# Power.net
KiCad netlist of a schematic drawn in Altium Designer
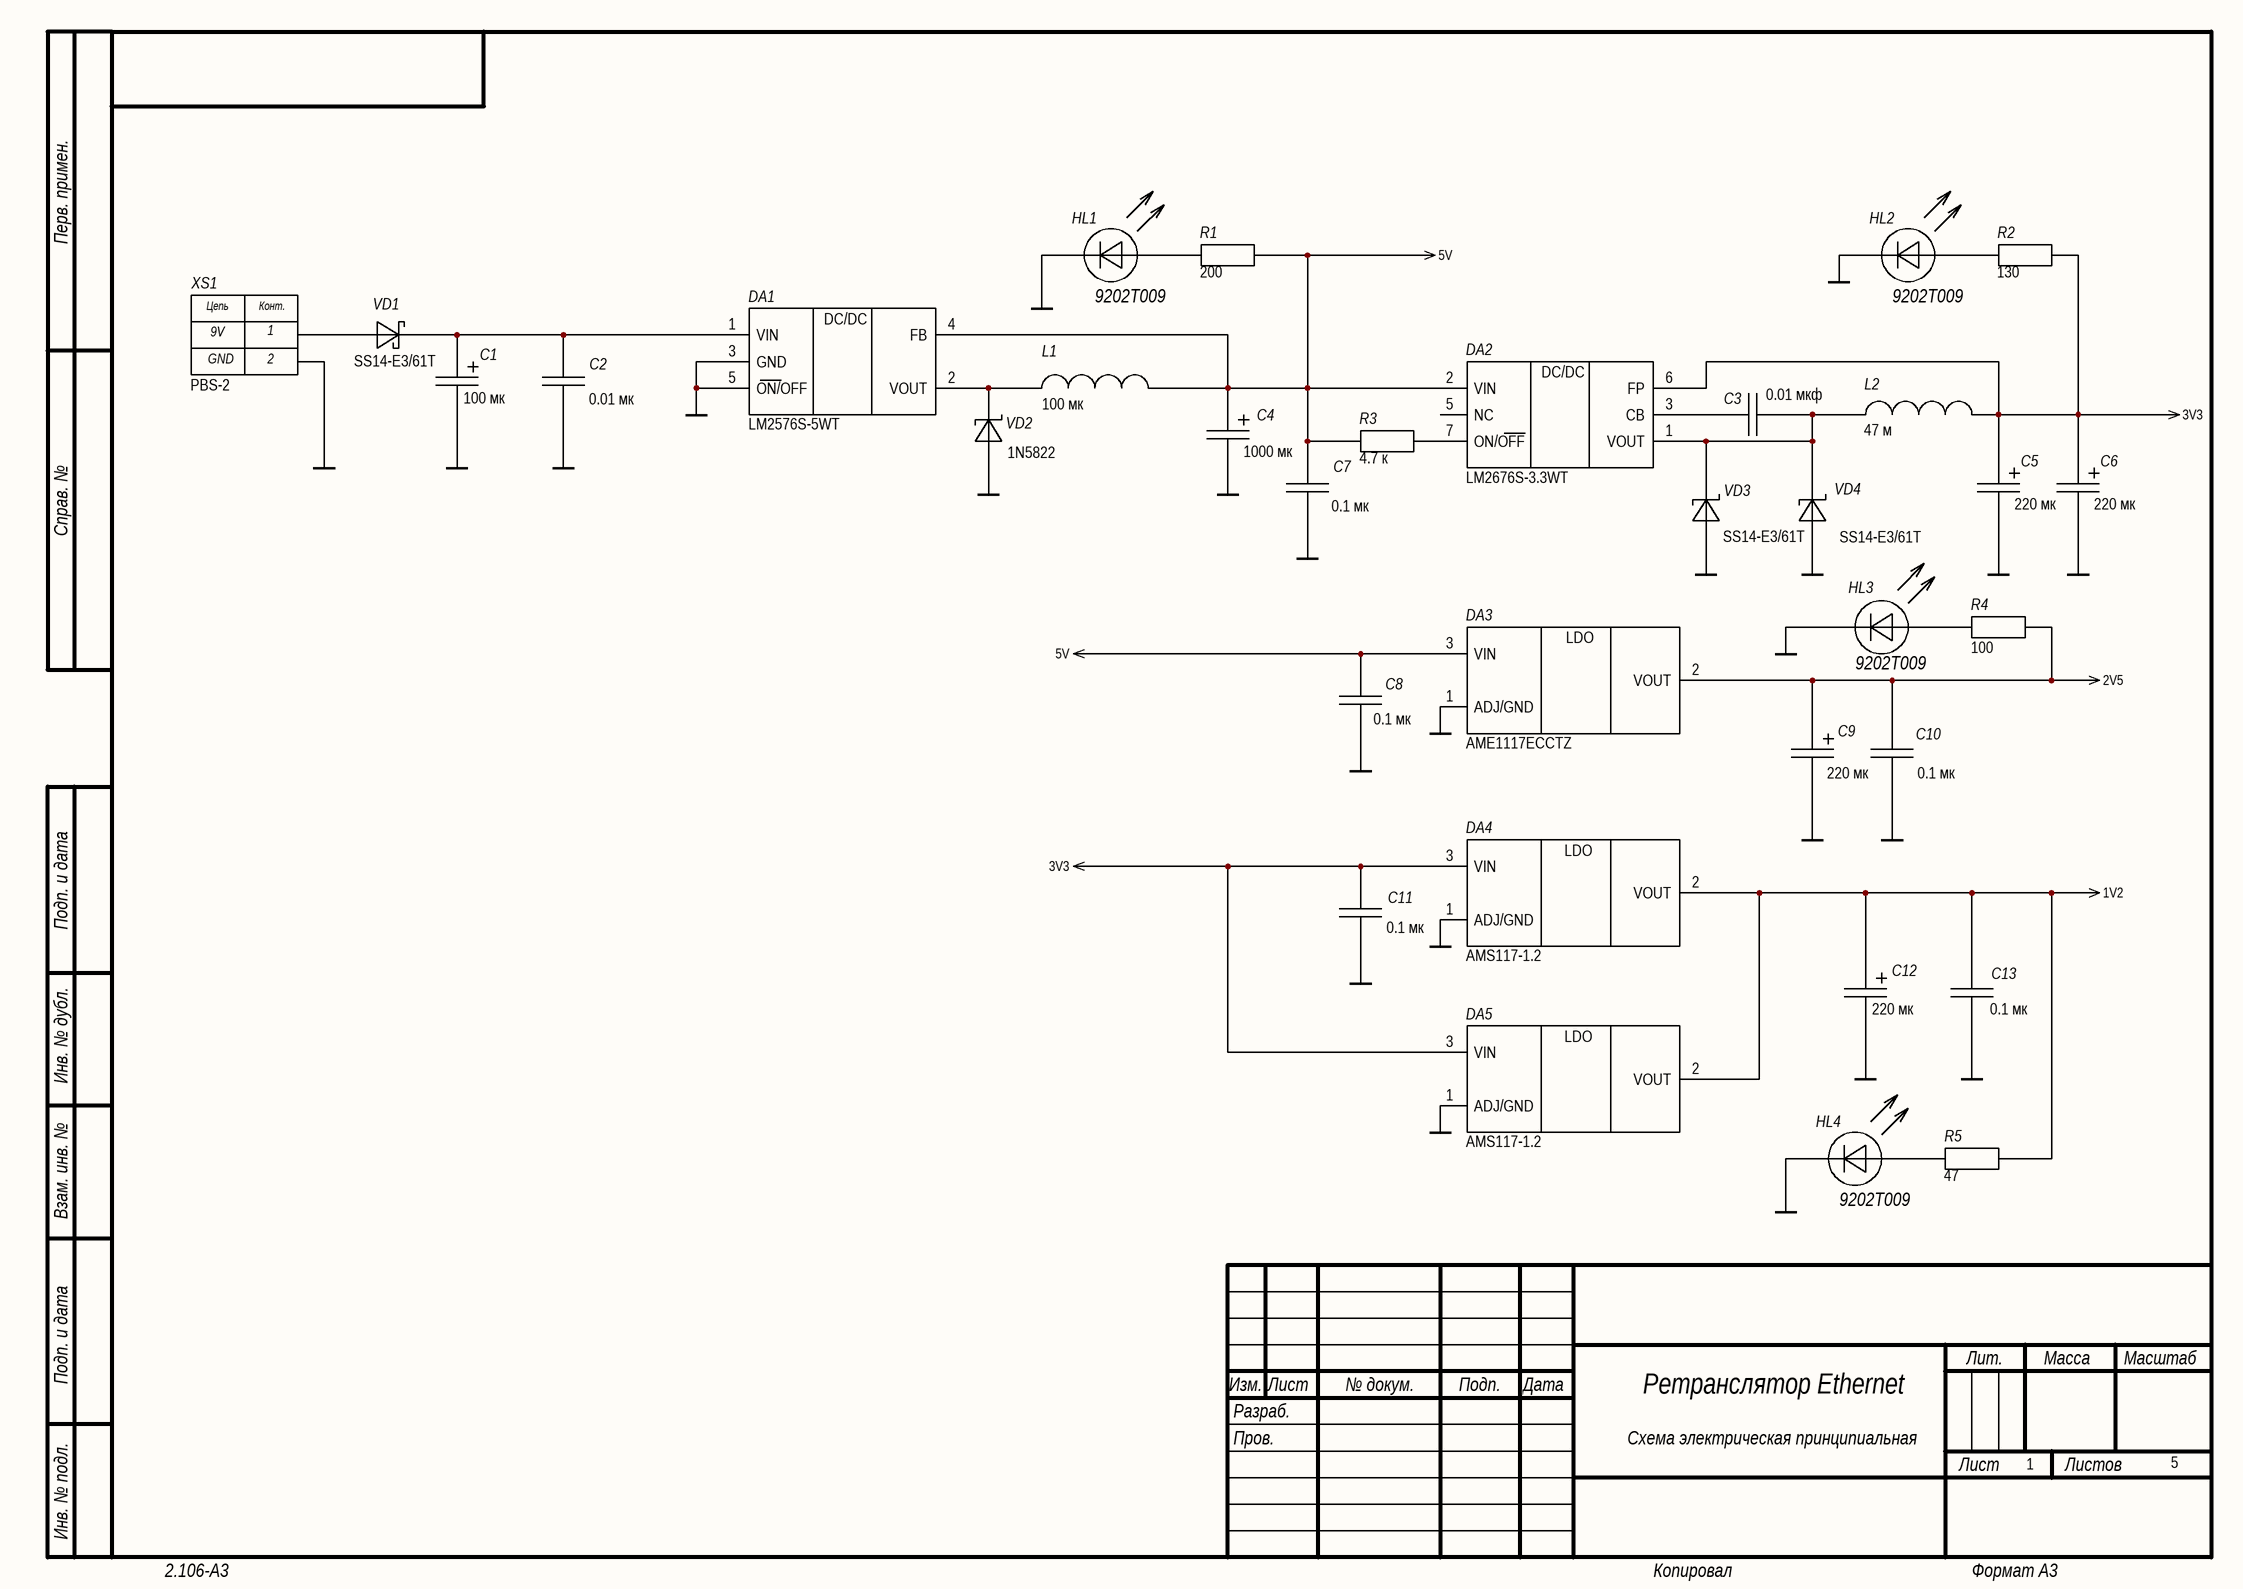
[diagram p0: Power.SchDoc]

(export (version "E")
  (design (tool "Eeschema 10.0.6"))
  (components
    (comp (ref "C1") (value "~") (libsource (lib "Schlib1") (part "C_POL")))
    (comp (ref "C2") (value "~") (libsource (lib "Schlib1") (part "C")))
    (comp (ref "C3") (value "~") (libsource (lib "Schlib1") (part "C")))
    (comp (ref "C4") (value "~") (libsource (lib "Schlib1") (part "C_POL")))
    (comp (ref "C5") (value "~") (libsource (lib "Schlib1") (part "C_POL")))
    (comp (ref "C6") (value "~") (libsource (lib "Schlib1") (part "C_POL")))
    (comp (ref "C7") (value "~") (libsource (lib "Schlib1") (part "C")))
    (comp (ref "C8") (value "~") (libsource (lib "Schlib1") (part "C")))
    (comp (ref "C9") (value "~") (libsource (lib "Schlib1") (part "C_POL")))
    (comp (ref "C10") (value "~") (libsource (lib "Schlib1") (part "C")))
    (comp (ref "C11") (value "~") (libsource (lib "Schlib1") (part "C")))
    (comp (ref "C12") (value "~") (libsource (lib "Schlib1") (part "C_POL")))
    (comp (ref "C13") (value "~") (libsource (lib "Schlib1") (part "C")))
    (comp (ref "DA1") (value "LM2576S-5WT") (libsource (lib "Schlib1") (part "LM2576_DCDC")))
    (comp (ref "DA2") (value "LM2676S-3.3WT") (libsource (lib "Schlib1") (part "LM2676_LDO_3v3")))
    (comp (ref "DA3") (value "AME1117ECCTZ") (libsource (lib "Schlib1") (part "AME1117ECCTZ_LDO_1.8v")))
    (comp (ref "DA4") (value "AMS117-1.2") (libsource (lib "Schlib1") (part "AME1117ACCTZ_LDO_1.2v")))
    (comp (ref "DA5") (value "AMS117-1.2") (libsource (lib "Schlib1") (part "AME1117ACCTZ_LDO_1.2v")))
    (comp (ref "HL1")
      (value "9202T009")
      (fields (field (name "VALUEMANUFACTURERPARTNUMBER") "fyls-0603urc"))
      (libsource (lib "Schlib1") (part "Led_blue"))
    )
    (comp (ref "HL2")
      (value "9202T009")
      (fields (field (name "VALUEMANUFACTURERPARTNUMBER") "fyls-0603urc"))
      (libsource (lib "Schlib1") (part "Led_blue"))
    )
    (comp (ref "HL3")
      (value "9202T009")
      (fields (field (name "VALUEMANUFACTURERPARTNUMBER") "fyls-0603urc"))
      (libsource (lib "Schlib1") (part "Led_blue"))
    )
    (comp (ref "HL4")
      (value "9202T009")
      (fields (field (name "VALUEMANUFACTURERPARTNUMBER") "fyls-0603urc"))
      (libsource (lib "Schlib1") (part "Led_blue"))
    )
    (comp (ref "L1") (value "L") (libsource (lib "Schlib1") (part "L")))
    (comp (ref "L2") (value "L") (libsource (lib "Schlib1") (part "L")))
    (comp (ref "R1") (value "200") (libsource (lib "Schlib1") (part "R")))
    (comp (ref "R2") (value "130") (libsource (lib "Schlib1") (part "R")))
    (comp (ref "R3") (value "4.7 к") (libsource (lib "Schlib1") (part "R")))
    (comp (ref "R4") (value "100") (libsource (lib "Schlib1") (part "R")))
    (comp (ref "R5") (value "47") (libsource (lib "Schlib1") (part "R")))
    (comp (ref "VD1")
      (value "*")
      (fields (field (name "VALUEMANUFACTURERPARTNUMBER") "BAT54HT1G"))
      (libsource (lib "Schlib1") (part "shotki"))
    )
    (comp (ref "VD2")
      (value "*")
      (fields (field (name "VALUEMANUFACTURERPARTNUMBER") "BAT54HT1G"))
      (libsource (lib "Schlib1") (part "Diode"))
    )
    (comp (ref "VD3")
      (value "*")
      (fields (field (name "VALUEMANUFACTURERPARTNUMBER") "BAT54HT1G"))
      (libsource (lib "Schlib1") (part "Diode"))
    )
    (comp (ref "VD4")
      (value "*")
      (fields (field (name "VALUEMANUFACTURERPARTNUMBER") "BAT54HT1G"))
      (libsource (lib "Schlib1") (part "Diode"))
    )
    (comp (ref "XS1") (value "Header") (libsource (lib "Schlib1") (part "Header")))
  )
  (nets
    (net (code "1") (name "1V2") (class "Default")
      (node (ref "C12") (pin "2") (pintype "passive"))
      (node (ref "C13") (pin "2") (pintype "passive"))
      (node (ref "DA4") (pin "2") (pinfunction "VOUT_2") (pintype "passive"))
      (node (ref "DA5") (pin "2") (pinfunction "VOUT_2") (pintype "passive"))
      (node (ref "R5") (pin "1") (pinfunction "1_1") (pintype "passive"))
    )
    (net (code "2") (name "2V5") (class "Default")
      (node (ref "C10") (pin "2") (pintype "passive"))
      (node (ref "C9") (pin "2") (pintype "passive"))
      (node (ref "DA3") (pin "2") (pinfunction "VOUT_2") (pintype "passive"))
      (node (ref "R4") (pin "1") (pinfunction "1_1") (pintype "passive"))
    )
    (net (code "3") (name "3V3") (class "Default")
      (node (ref "C11") (pin "2") (pintype "passive"))
      (node (ref "C5") (pin "2") (pintype "passive"))
      (node (ref "C6") (pin "2") (pintype "passive"))
      (node (ref "DA2") (pin "6") (pinfunction "FP_6") (pintype "passive"))
      (node (ref "DA4") (pin "3") (pinfunction "VIN_3") (pintype "passive"))
      (node (ref "DA5") (pin "3") (pinfunction "VIN_3") (pintype "passive"))
      (node (ref "L2") (pin "2") (pinfunction "2_2") (pintype "passive"))
      (node (ref "R2") (pin "1") (pinfunction "1_1") (pintype "passive"))
    )
    (net (code "4") (name "5V") (class "Default")
      (node (ref "C4") (pin "2") (pintype "passive"))
      (node (ref "C7") (pin "2") (pintype "passive"))
      (node (ref "C8") (pin "2") (pintype "passive"))
      (node (ref "DA1") (pin "4") (pinfunction "FB_4") (pintype "passive"))
      (node (ref "DA2") (pin "2") (pinfunction "VIN_2") (pintype "passive"))
      (node (ref "DA3") (pin "3") (pinfunction "VIN_3") (pintype "passive"))
      (node (ref "L1") (pin "2") (pinfunction "2_2") (pintype "passive"))
      (node (ref "R1") (pin "1") (pinfunction "1_1") (pintype "passive"))
      (node (ref "R3") (pin "2") (pinfunction "2_2") (pintype "passive"))
    )
    (net (code "5") (name "GND") (class "Default")
      (node (ref "C1") (pin "1") (pintype "passive"))
      (node (ref "C10") (pin "1") (pintype "passive"))
      (node (ref "C11") (pin "1") (pintype "passive"))
      (node (ref "C12") (pin "1") (pintype "passive"))
      (node (ref "C13") (pin "1") (pintype "passive"))
      (node (ref "C2") (pin "1") (pintype "passive"))
      (node (ref "C5") (pin "1") (pintype "passive"))
      (node (ref "C6") (pin "1") (pintype "passive"))
      (node (ref "C7") (pin "1") (pintype "passive"))
      (node (ref "C8") (pin "1") (pintype "passive"))
      (node (ref "C9") (pin "1") (pintype "passive"))
      (node (ref "DA1") (pin "3") (pinfunction "GND_3") (pintype "passive"))
      (node (ref "DA1") (pin "5") (pinfunction "ON/OFF_5") (pintype "passive"))
      (node (ref "DA3") (pin "1") (pinfunction "ADJ/GND_1") (pintype "passive"))
      (node (ref "DA4") (pin "1") (pinfunction "ADJ/GND_1") (pintype "passive"))
      (node (ref "DA5") (pin "1") (pinfunction "ADJ/GND_1") (pintype "passive"))
      (node (ref "HL1") (pin "2") (pintype "passive"))
      (node (ref "HL2") (pin "2") (pintype "passive"))
      (node (ref "HL3") (pin "2") (pintype "passive"))
      (node (ref "HL4") (pin "2") (pintype "passive"))
      (node (ref "VD2") (pin "1") (pintype "passive"))
      (node (ref "VD3") (pin "1") (pintype "passive"))
      (node (ref "VD4") (pin "1") (pintype "passive"))
      (node (ref "XS1") (pin "2") (pinfunction "2_2") (pintype "passive"))
    )
    (net (code "6") (name "Net-(DA1-VIN)") (class "Default")
      (node (ref "C1") (pin "2") (pintype "passive"))
      (node (ref "C2") (pin "2") (pintype "passive"))
      (node (ref "DA1") (pin "1") (pinfunction "VIN_1") (pintype "passive"))
      (node (ref "VD1") (pin "2") (pintype "passive"))
    )
    (net (code "7") (name "Net-(DA1-VOUT)") (class "Default")
      (node (ref "DA1") (pin "2") (pinfunction "VOUT_2") (pintype "passive"))
      (node (ref "L1") (pin "1") (pinfunction "1_1") (pintype "passive"))
      (node (ref "VD2") (pin "2") (pintype "passive"))
    )
    (net (code "8") (name "Net-(DA2-CB)") (class "Default")
      (node (ref "C3") (pin "2") (pintype "passive"))
      (node (ref "DA2") (pin "3") (pinfunction "CB_3") (pintype "passive"))
    )
    (net (code "9") (name "Net-(DA2-ON{slash}OFF)") (class "Default")
      (node (ref "DA2") (pin "7") (pinfunction "ON/OFF_7") (pintype "passive"))
      (node (ref "R3") (pin "1") (pinfunction "1_1") (pintype "passive"))
    )
    (net (code "10") (name "Net-(DA2-VOUT)") (class "Default")
      (node (ref "C3") (pin "1") (pintype "passive"))
      (node (ref "DA2") (pin "1") (pinfunction "VOUT_1") (pintype "passive"))
      (node (ref "L2") (pin "1") (pinfunction "1_1") (pintype "passive"))
      (node (ref "VD3") (pin "2") (pintype "passive"))
      (node (ref "VD4") (pin "2") (pintype "passive"))
    )
    (net (code "11") (name "Net-(HL1-Pad1)") (class "Default")
      (node (ref "HL1") (pin "1") (pintype "passive"))
      (node (ref "R1") (pin "2") (pinfunction "2_2") (pintype "passive"))
    )
    (net (code "12") (name "Net-(HL2-Pad1)") (class "Default")
      (node (ref "HL2") (pin "1") (pintype "passive"))
      (node (ref "R2") (pin "2") (pinfunction "2_2") (pintype "passive"))
    )
    (net (code "13") (name "Net-(HL3-Pad1)") (class "Default")
      (node (ref "HL3") (pin "1") (pintype "passive"))
      (node (ref "R4") (pin "2") (pinfunction "2_2") (pintype "passive"))
    )
    (net (code "14") (name "Net-(HL4-Pad1)") (class "Default")
      (node (ref "HL4") (pin "1") (pintype "passive"))
      (node (ref "R5") (pin "2") (pinfunction "2_2") (pintype "passive"))
    )
    (net (code "15") (name "Net-(VD1-Pad1)") (class "Default")
      (node (ref "VD1") (pin "1") (pintype "passive"))
      (node (ref "XS1") (pin "1") (pinfunction "1_1") (pintype "passive"))
    )
    (net (code "16") (name "unconnected-(C4-Pad1)") (class "Default")
      (node (ref "C4") (pin "1") (pintype "passive"))
    )
    (net (code "17") (name "unconnected-(DA2-NC-Pad5)") (class "Default")
      (node (ref "DA2") (pin "5") (pinfunction "NC_5") (pintype "passive"))
    )
  )
)
